# RF_Bypass.net
KiCad netlist of a schematic drawn in Altium Designer
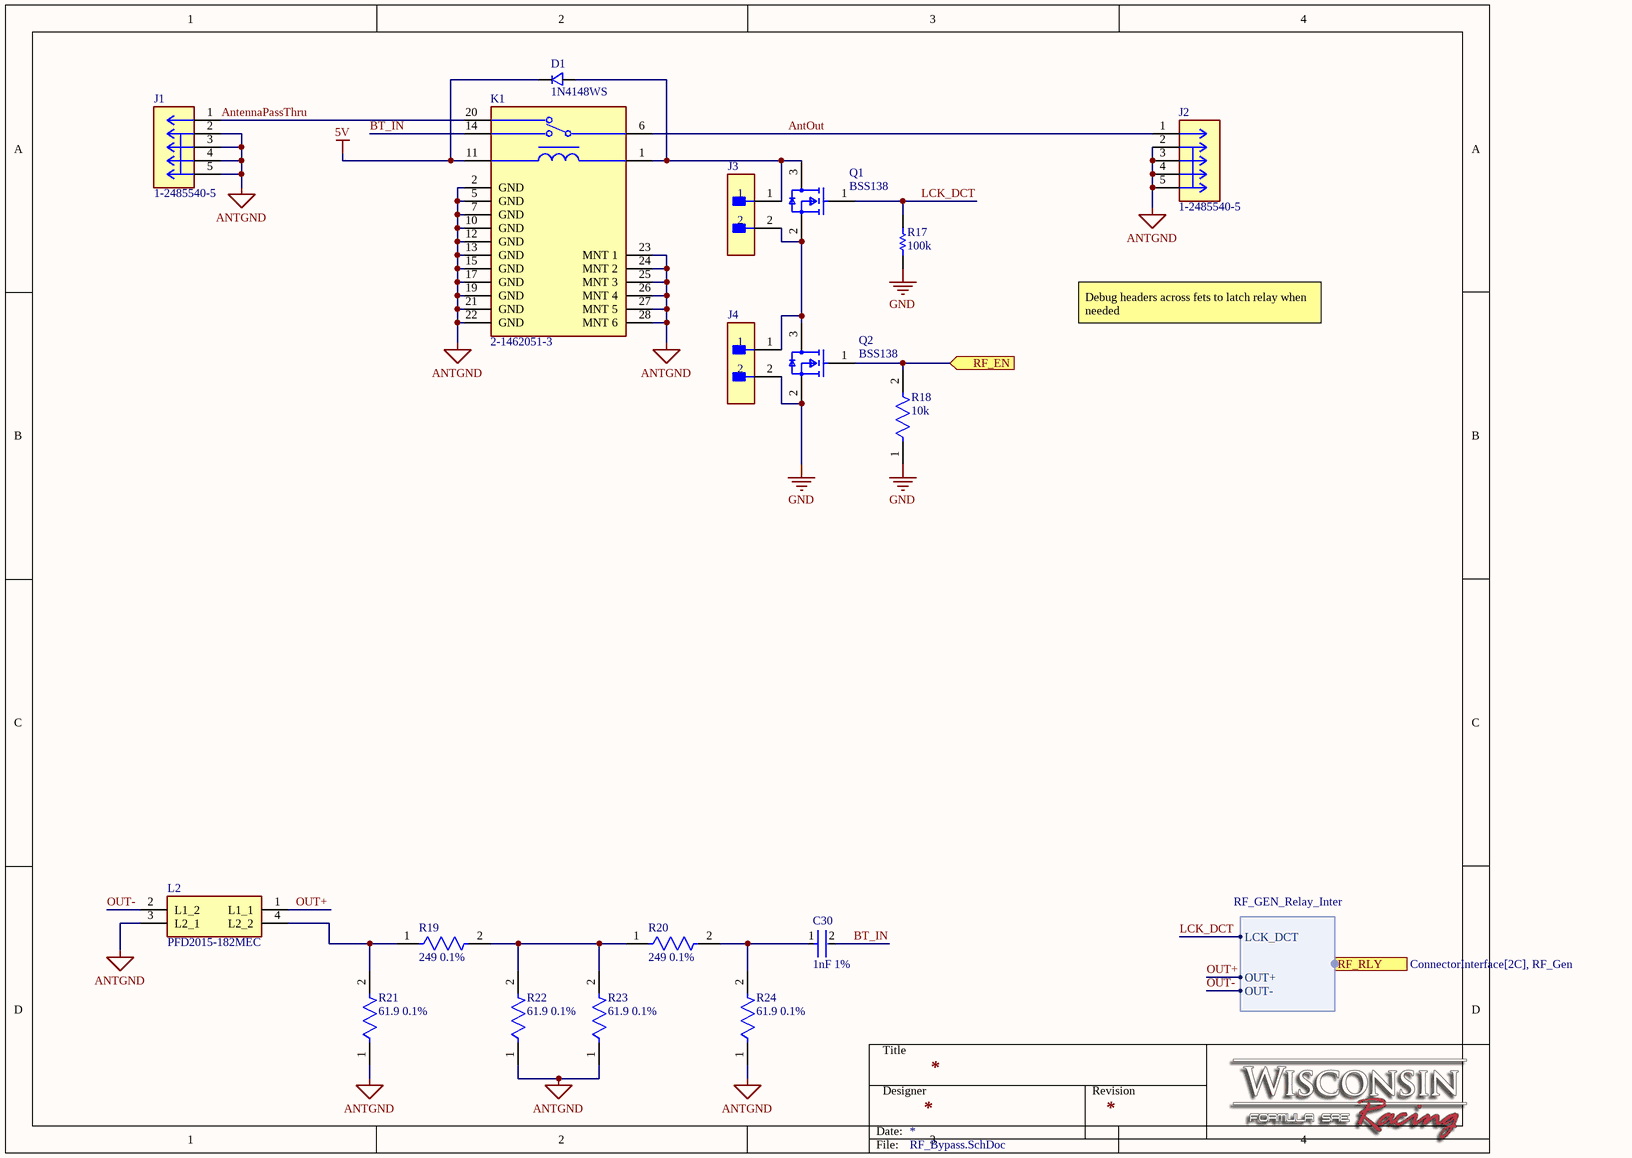
[diagram p0: RF_Bypass.SchDoc]

(export (version "E")
  (design (tool "Eeschema 10.0.6"))
  (components
    (comp (ref "C30")
      (value "1nF 1%")
      (footprint "FP-GRT155-0_05-IPC_A")
      (description "Multi-Layer Ceramic Capacitor 1nF 50V C0G ±1% 0402 Paper T/R\r\n\r\nGRT1555C1H102FA02D")
      (libsource (lib "Altium Content Vault") (part "02cd4be3c70576c341d710602a673aa"))
    )
    (comp (ref "D1")
      (value "1N4148WS")
      (footprint "SODFL250X90-2N")
      (description "Diode")
      (libsource (lib "University of Wisconsin Formula FSAE") (part "1N4148WS"))
    )
    (comp (ref "J1")
      (value "1-2485540-5")
      (footprint "1-2485540-5-Footprint-1")
      (libsource (lib "") (part "New symbol 1_1"))
    )
    (comp (ref "J2")
      (value "1-2485540-5")
      (footprint "1-2485540-5-Footprint-1")
      (libsource (lib "University of Wisconsin Formula FSAE") (part "New symbol 1"))
    )
    (comp (ref "J3")
      (value "TSM-102-01-T-SV-TR")
      (footprint "FP-TSM-102-01-T-SV-TR-MFG")
      (description "CONN HEADER SMD 2POS 2.54MM")
      (libsource (lib "Altium Content Vault") (part "3bc925449376181038e59eaffc5286c"))
    )
    (comp (ref "J4")
      (value "TSM-102-01-T-SV-TR")
      (footprint "FP-TSM-102-01-T-SV-TR-MFG")
      (description "CONN HEADER SMD 2POS 2.54MM")
      (libsource (lib "Altium Content Vault") (part "3bc925449376181038e59eaffc5286c"))
    )
    (comp (ref "K1")
      (value "2-1462051-3")
      (footprint "FP-2-1462051-3-MFG")
      (description "RELAY RF SPDT 2A 5V")
      (libsource (lib "Altium Content Vault") (part "1f4026939bf67184423d2831d7f6c24"))
    )
    (comp (ref "L2")
      (value "PFD2015-182MEC")
      (footprint "SamacSys:PFD2015102MEB")
      (description "Inductor")
      (fields
        (field (name "MANUFACTURER_PART_NUMBER") "PFD2015-102MEB")
        (field (name "MOUSER PART NUMBER") "994-PFD2015-102MEB")
      )
      (libsource (lib "*") (part "PFD2015-102MEB"))
    )
    (comp (ref "Q1")
      (value "BSS138")
      (footprint "FP-318-08-IPC_B")
      (description "MOSFET N-CH 50V 220MA SOT-23")
      (libsource (lib "Altium Content Vault") (part "3b9c635fedb024a5347a57b145af9cc"))
    )
    (comp (ref "Q2")
      (value "BSS138")
      (footprint "FP-318-08-IPC_B")
      (description "MOSFET N-CH 50V 220MA SOT-23")
      (libsource (lib "Altium Content Vault") (part "3b9c635fedb024a5347a57b145af9cc"))
    )
    (comp (ref "R17")
      (value "100k")
      (footprint "RESC1005X40X25NL05T10")
      (fields (field (name "PART NUMBER") "RC0402FR-07100KL") (field (name "MANUFACTURER") "Yageo / Phycomp"))
      (libsource (lib "Altium Content Vault") (part "RES"))
    )
    (comp (ref "R18")
      (value "10k")
      (footprint "FP-RC0402-0_4-IPC_C")
      (description "RES 10K OHM 5% 1/16W 0402")
      (fields (field (name "TOLERANCE") "5%"))
      (libsource (lib "Altium Content Vault") (part "1029c3af85768c4190bb7ad29bc67b5"))
    )
    (comp (ref "R19")
      (value "249 0.1%")
      (footprint "FP-RT0402-MFG")
      (description "RES SMD 249 OHM 0.1% 1/16W 0402")
      (fields
        (field (name "MANUFACTURER") "Yageo")
        (field (name "OCTOPART") "https://octopart.com/rt0402brd07249rl-yageo-1467928")
      )
      (libsource (lib "Altium Content Vault") (part "1029c3af85768c4190bb7ad29bc67b5"))
    )
    (comp (ref "R20")
      (value "249 0.1%")
      (footprint "FP-RT0402-MFG")
      (description "RES SMD 249 OHM 0.1% 1/16W 0402")
      (fields
        (field (name "MANUFACTURER") "Yageo")
        (field (name "OCTOPART") "https://octopart.com/rt0402brd07249rl-yageo-1467928")
      )
      (libsource (lib "Altium Content Vault") (part "1029c3af85768c4190bb7ad29bc67b5"))
    )
    (comp (ref "R21")
      (value "61.9 0.1%")
      (footprint "FP-RP73P-1E-MFG")
      (description "RP73P 0402 61.9Ω 0.1W 25ppm/°C 0.10% 50V")
      (fields
        (field (name "OCTOPART") "https://octopart.com/rp73pf1e61r9btd-te+connectivity-89230235")
        (field (name "MANUFACTURER") "TE Connectivity")
      )
      (libsource (lib "Altium Content Vault") (part "1029c3af85768c4190bb7ad29bc67b5"))
    )
    (comp (ref "R22")
      (value "61.9 0.1%")
      (footprint "FP-RP73P-1E-MFG")
      (description "RP73P 0402 61.9Ω 0.1W 25ppm/°C 0.10% 50V")
      (fields
        (field (name "OCTOPART") "https://octopart.com/rp73pf1e61r9btd-te+connectivity-89230235")
        (field (name "MANUFACTURER") "TE Connectivity")
      )
      (libsource (lib "Altium Content Vault") (part "1029c3af85768c4190bb7ad29bc67b5"))
    )
    (comp (ref "R23")
      (value "61.9 0.1%")
      (footprint "FP-RP73P-1E-MFG")
      (description "RP73P 0402 61.9Ω 0.1W 25ppm/°C 0.10% 50V")
      (fields
        (field (name "OCTOPART") "https://octopart.com/rp73pf1e61r9btd-te+connectivity-89230235")
        (field (name "MANUFACTURER") "TE Connectivity")
      )
      (libsource (lib "Altium Content Vault") (part "1029c3af85768c4190bb7ad29bc67b5"))
    )
    (comp (ref "R24")
      (value "61.9 0.1%")
      (footprint "FP-RP73P-1E-MFG")
      (description "RP73P 0402 61.9Ω 0.1W 25ppm/°C 0.10% 50V")
      (fields
        (field (name "OCTOPART") "https://octopart.com/rp73pf1e61r9btd-te+connectivity-89230235")
        (field (name "MANUFACTURER") "TE Connectivity")
      )
      (libsource (lib "Altium Content Vault") (part "1029c3af85768c4190bb7ad29bc67b5"))
    )
  )
  (nets
    (net (code "2") (name "/AntOut") (class "Default")
      (node (ref "J2") (pin "1") (pinfunction "1_1") (pintype "passive"))
      (node (ref "K1") (pin "6") (pinfunction "6_6") (pintype "passive"))
    )
    (net (code "3") (name "/AntennaPassThru") (class "Default")
      (node (ref "J1") (pin "1") (pinfunction "1_1") (pintype "passive"))
      (node (ref "K1") (pin "20") (pinfunction "20_20") (pintype "passive"))
    )
    (net (code "4") (name "/BT_IN") (class "Default")
      (node (ref "C30") (pin "2") (pinfunction "2_2") (pintype "passive"))
      (node (ref "K1") (pin "14") (pinfunction "14_14") (pintype "passive"))
    )
    (net (code "5") (name "/LCK_DCT") (class "Default")
      (node (ref "Q1") (pin "1") (pinfunction "G_1") (pintype "passive"))
      (node (ref "R17") (pin "2") (pinfunction "2_2") (pintype "passive"))
    )
    (net (code "6") (name "/OUT+") (class "Default")
      (node (ref "L2") (pin "1") (pinfunction "L1_1_1") (pintype "passive"))
    )
    (net (code "7") (name "/OUT-") (class "Default")
      (node (ref "L2") (pin "2") (pinfunction "L1_2_2") (pintype "passive"))
    )
    (net (code "8") (name "/RF_EN") (class "Default")
      (node (ref "Q2") (pin "1") (pinfunction "G_1") (pintype "passive"))
      (node (ref "R18") (pin "2") (pinfunction "2_2") (pintype "passive"))
    )
    (net (code "10") (name "5V") (class "Default")
      (node (ref "D1") (pin "1") (pinfunction "1_1") (pintype "passive"))
      (node (ref "K1") (pin "11") (pinfunction "-_11") (pintype "passive"))
    )
    (net (code "11") (name "ANTGND") (class "Default")
      (node (ref "J1") (pin "2") (pinfunction "2_2") (pintype "passive"))
      (node (ref "J1") (pin "3") (pinfunction "3_3") (pintype "passive"))
      (node (ref "J1") (pin "4") (pinfunction "4_4") (pintype "passive"))
      (node (ref "J1") (pin "5") (pinfunction "5_5") (pintype "passive"))
      (node (ref "J2") (pin "2") (pinfunction "2_2") (pintype "passive"))
      (node (ref "J2") (pin "3") (pinfunction "3_3") (pintype "passive"))
      (node (ref "J2") (pin "4") (pinfunction "4_4") (pintype "passive"))
      (node (ref "J2") (pin "5") (pinfunction "5_5") (pintype "passive"))
      (node (ref "K1") (pin "10") (pinfunction "GND_10") (pintype "power_in"))
      (node (ref "K1") (pin "12") (pinfunction "GND_12") (pintype "power_in"))
      (node (ref "K1") (pin "13") (pinfunction "GND_13") (pintype "power_in"))
      (node (ref "K1") (pin "15") (pinfunction "GND_15") (pintype "power_in"))
      (node (ref "K1") (pin "17") (pinfunction "GND_17") (pintype "power_in"))
      (node (ref "K1") (pin "19") (pinfunction "GND_19") (pintype "power_in"))
      (node (ref "K1") (pin "2") (pinfunction "GND_2") (pintype "power_in"))
      (node (ref "K1") (pin "21") (pinfunction "GND_21") (pintype "power_in"))
      (node (ref "K1") (pin "22") (pinfunction "GND_22") (pintype "power_in"))
      (node (ref "K1") (pin "23") (pinfunction "MNT_1_23") (pintype "passive"))
      (node (ref "K1") (pin "24") (pinfunction "MNT_2_24") (pintype "passive"))
      (node (ref "K1") (pin "25") (pinfunction "MNT_3_25") (pintype "passive"))
      (node (ref "K1") (pin "26") (pinfunction "MNT_4_26") (pintype "passive"))
      (node (ref "K1") (pin "27") (pinfunction "MNT_5_27") (pintype "passive"))
      (node (ref "K1") (pin "28") (pinfunction "MNT_6_28") (pintype "passive"))
      (node (ref "K1") (pin "5") (pinfunction "GND_5") (pintype "power_in"))
      (node (ref "K1") (pin "7") (pinfunction "GND_7") (pintype "power_in"))
      (node (ref "L2") (pin "3") (pinfunction "L2_1_3") (pintype "passive"))
      (node (ref "R21") (pin "1") (pinfunction "1_1") (pintype "passive"))
      (node (ref "R22") (pin "1") (pinfunction "1_1") (pintype "passive"))
      (node (ref "R23") (pin "1") (pinfunction "1_1") (pintype "passive"))
      (node (ref "R24") (pin "1") (pinfunction "1_1") (pintype "passive"))
    )
    (net (code "12") (name "GND") (class "Default")
      (node (ref "J4") (pin "2") (pinfunction "2_2") (pintype "passive"))
      (node (ref "Q2") (pin "2") (pinfunction "S_2") (pintype "passive"))
      (node (ref "R17") (pin "1") (pinfunction "1_1") (pintype "passive"))
      (node (ref "R18") (pin "1") (pinfunction "1_1") (pintype "passive"))
    )
    (net (code "13") (name "Net-(C30-Pad1)") (class "Default")
      (node (ref "C30") (pin "1") (pinfunction "1_1") (pintype "passive"))
      (node (ref "R20") (pin "2") (pinfunction "2_2") (pintype "passive"))
      (node (ref "R24") (pin "2") (pinfunction "2_2") (pintype "passive"))
    )
    (net (code "14") (name "Net-(K1-+)") (class "Default")
      (node (ref "D1") (pin "2") (pinfunction "2_2") (pintype "passive"))
      (node (ref "J3") (pin "1") (pinfunction "1_1") (pintype "passive"))
      (node (ref "K1") (pin "1") (pinfunction "+_1") (pintype "passive"))
      (node (ref "Q1") (pin "3") (pinfunction "D_3") (pintype "passive"))
    )
    (net (code "15") (name "Net-(L2-L2_2)") (class "Default")
      (node (ref "L2") (pin "4") (pinfunction "L2_2_4") (pintype "passive"))
      (node (ref "R19") (pin "1") (pinfunction "1_1") (pintype "passive"))
      (node (ref "R21") (pin "2") (pinfunction "2_2") (pintype "passive"))
    )
    (net (code "16") (name "Net-(Q1-S)") (class "Default")
      (node (ref "J3") (pin "2") (pinfunction "2_2") (pintype "passive"))
      (node (ref "J4") (pin "1") (pinfunction "1_1") (pintype "passive"))
      (node (ref "Q1") (pin "2") (pinfunction "S_2") (pintype "passive"))
      (node (ref "Q2") (pin "3") (pinfunction "D_3") (pintype "passive"))
    )
    (net (code "17") (name "Net-(R19-Pad2)") (class "Default")
      (node (ref "R19") (pin "2") (pinfunction "2_2") (pintype "passive"))
      (node (ref "R20") (pin "1") (pinfunction "1_1") (pintype "passive"))
      (node (ref "R22") (pin "2") (pinfunction "2_2") (pintype "passive"))
      (node (ref "R23") (pin "2") (pinfunction "2_2") (pintype "passive"))
    )
  )
)
